# Oscar_MainBoard_UartUSB.net
KiCad netlist of a schematic drawn in Altium Designer
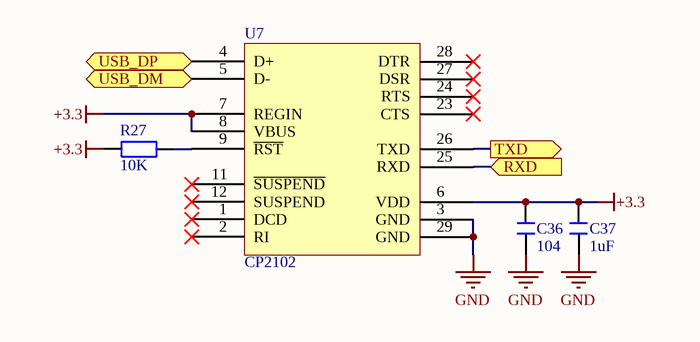
[diagram p0: Oscar_MainBoard_UartUSB.SchDoc]

(export (version "E")
  (design (tool "Eeschema 10.0.6"))
  (components
    (comp (ref "C36")
      (value "104")
      (footprint "C 0402_L")
      (description "贴片电容")
      (libsource (lib "0.1 - 电阻-电容-电感") (part "C"))
    )
    (comp (ref "C37")
      (value "1uF")
      (footprint "C 0402_L")
      (description "贴片电容")
      (libsource (lib "0.1 - 电阻-电容-电感") (part "C"))
    )
    (comp (ref "R27")
      (value "10K")
      (footprint "R 0402_L")
      (description "贴片电阻")
      (libsource (lib "0.1 - 电阻-电容-电感") (part "R"))
    )
    (comp (ref "U7")
      (value "CP2102")
      (footprint "QFN28 5x5_N")
      (description "CP2102 uart usb")
      (libsource (lib "1.9 - CH340系列编程器芯片") (part "CP2102"))
    )
  )
  (nets
    (net (code "1") (name "+3.3") (class "Default")
      (node (ref "C36") (pin "2") (pinfunction "2_2") (pintype "passive"))
      (node (ref "C37") (pin "2") (pinfunction "2_2") (pintype "passive"))
      (node (ref "R27") (pin "1") (pinfunction "1_1") (pintype "passive"))
      (node (ref "U7") (pin "6") (pinfunction "VDD_6") (pintype "passive"))
      (node (ref "U7") (pin "7") (pinfunction "REGIN_7") (pintype "passive"))
      (node (ref "U7") (pin "8") (pinfunction "VBUS_8") (pintype "passive"))
    )
    (net (code "2") (name "/RXD") (class "Default")
      (node (ref "U7") (pin "25") (pinfunction "RXD_25") (pintype "passive"))
    )
    (net (code "3") (name "/TXD") (class "Default")
      (node (ref "U7") (pin "26") (pinfunction "TXD_26") (pintype "passive"))
    )
    (net (code "4") (name "/USB_DM") (class "Default")
      (node (ref "U7") (pin "5") (pinfunction "D-_5") (pintype "passive"))
    )
    (net (code "5") (name "/USB_DP") (class "Default")
      (node (ref "U7") (pin "4") (pinfunction "D+_4") (pintype "passive"))
    )
    (net (code "6") (name "GND") (class "Default")
      (node (ref "C36") (pin "1") (pinfunction "1_1") (pintype "passive"))
      (node (ref "C37") (pin "1") (pinfunction "1_1") (pintype "passive"))
      (node (ref "U7") (pin "29") (pinfunction "GND_29") (pintype "passive"))
      (node (ref "U7") (pin "3") (pinfunction "GND_3") (pintype "passive"))
    )
    (net (code "7") (name "Net-(U7-~{RST})") (class "Default")
      (node (ref "R27") (pin "2") (pinfunction "2_2") (pintype "passive"))
      (node (ref "U7") (pin "9") (pinfunction "~{RST}_9") (pintype "passive"))
    )
    (net (code "8") (name "unconnected-(U7-CTS-Pad23)") (class "Default")
      (node (ref "U7") (pin "23") (pinfunction "CTS_23") (pintype "passive+no_connect"))
    )
    (net (code "9") (name "unconnected-(U7-DCD-Pad1)") (class "Default")
      (node (ref "U7") (pin "1") (pinfunction "DCD_1") (pintype "passive+no_connect"))
    )
    (net (code "10") (name "unconnected-(U7-DSR-Pad27)") (class "Default")
      (node (ref "U7") (pin "27") (pinfunction "DSR_27") (pintype "passive+no_connect"))
    )
    (net (code "11") (name "unconnected-(U7-DTR-Pad28)") (class "Default")
      (node (ref "U7") (pin "28") (pinfunction "DTR_28") (pintype "passive+no_connect"))
    )
    (net (code "12") (name "unconnected-(U7-RI-Pad2)") (class "Default")
      (node (ref "U7") (pin "2") (pinfunction "RI_2") (pintype "passive+no_connect"))
    )
    (net (code "13") (name "unconnected-(U7-RTS-Pad24)") (class "Default")
      (node (ref "U7") (pin "24") (pinfunction "RTS_24") (pintype "passive+no_connect"))
    )
    (net (code "14") (name "unconnected-(U7-SUSPEND-Pad12)") (class "Default")
      (node (ref "U7") (pin "12") (pinfunction "SUSPEND_12") (pintype "passive+no_connect"))
    )
    (net (code "15") (name "unconnected-(U7-~{SUSPEND}-Pad11)") (class "Default")
      (node (ref "U7") (pin "11") (pinfunction "~{SUSPEND}_11") (pintype "passive+no_connect"))
    )
  )
)
